# lidar_robot.net
KiCad netlist of a schematic drawn in EAGLE
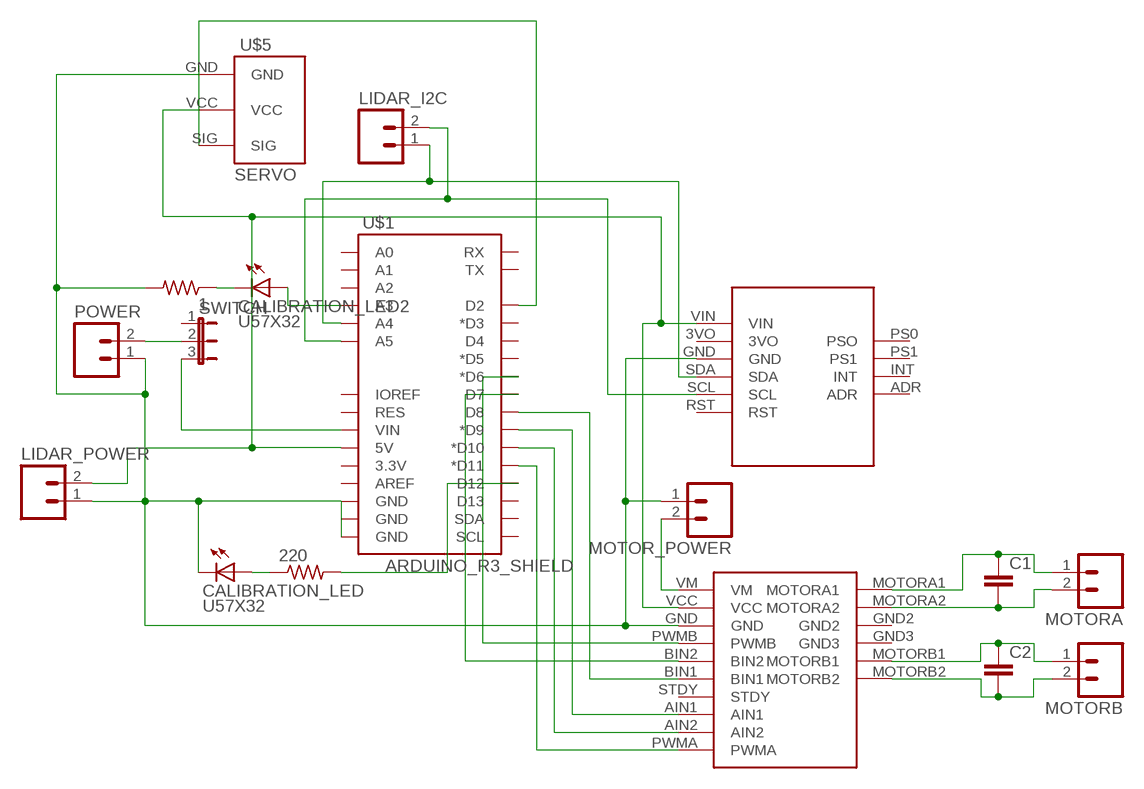
[diagram p0: schematic, sheet 1]

(export (version "E")
  (design (tool "Eeschema 10.0.6"))
  (components
    (comp (ref "1")
      (value "R-US_0207/10")
      (footprint "eagle-import:0207_10")
      (libsource (lib "eagle-import") (part "R-US_0207/10"))
    )
    (comp (ref "220")
      (value "R-US_0207/10")
      (footprint "eagle-import:0207_10")
      (libsource (lib "eagle-import") (part "R-US_0207/10"))
    )
    (comp (ref "C1")
      (value "C2.5/4")
      (footprint "eagle-import:C2.5-4")
      (libsource (lib "eagle-import") (part "C2.5/4"))
    )
    (comp (ref "C2")
      (value "C2.5/4")
      (footprint "eagle-import:C2.5-4")
      (libsource (lib "eagle-import") (part "C2.5/4"))
    )
    (comp (ref "CALIBRATION_LED")
      (value "U57X32")
      (footprint "eagle-import:U57X32")
      (libsource (lib "eagle-import") (part "U57X32"))
    )
    (comp (ref "CALIBRATION_LED2")
      (value "U57X32")
      (footprint "eagle-import:U57X32")
      (libsource (lib "eagle-import") (part "U57X32"))
    )
    (comp (ref "LIDAR_I2C")
      (value "M02LOCK")
      (footprint "eagle-import:1X02_LOCK")
      (libsource (lib "eagle-import") (part "M02LOCK"))
    )
    (comp (ref "LIDAR_POWER")
      (value "M02LOCK")
      (footprint "eagle-import:1X02_LOCK")
      (libsource (lib "eagle-import") (part "M02LOCK"))
    )
    (comp (ref "MOTORA")
      (value "M02LOCK")
      (footprint "eagle-import:1X02_LOCK")
      (libsource (lib "eagle-import") (part "M02LOCK"))
    )
    (comp (ref "MOTORB")
      (value "M02LOCK")
      (footprint "eagle-import:1X02_LOCK")
      (libsource (lib "eagle-import") (part "M02LOCK"))
    )
    (comp (ref "MOTOR_POWER")
      (value "M02LOCK")
      (footprint "eagle-import:1X02_LOCK")
      (libsource (lib "eagle-import") (part "M02LOCK"))
    )
    (comp (ref "POWER")
      (value "M02LOCK")
      (footprint "eagle-import:1X02_LOCK")
      (libsource (lib "eagle-import") (part "M02LOCK"))
    )
    (comp (ref "SWITCH")
      (value "JP2E")
      (footprint "eagle-import:JP2")
      (libsource (lib "eagle-import") (part "JP2E"))
    )
    (comp (ref "U$1")
      (value "ARDUINO_R3_SHIELD")
      (footprint "eagle-import:UNO_R3_SHIELD")
      (libsource (lib "eagle-import") (part "ARDUINO_R3_SHIELD"))
    )
    (comp (ref "U$2")
      (value "BN0055")
      (footprint "eagle-import:BN0055")
      (libsource (lib "eagle-import") (part "BN0055"))
    )
    (comp (ref "U$3")
      (value "TB6612")
      (footprint "eagle-import:TB6612")
      (libsource (lib "eagle-import") (part "TB6612"))
    )
    (comp (ref "U$5")
      (value "SERVO")
      (footprint "eagle-import:SERVO")
      (libsource (lib "eagle-import") (part "SERVO"))
    )
  )
  (nets
    (net (code "1") (name "Net-(220-Pad1)") (class "Default")
      (node (ref "220") (pin "1") (pinfunction "1_1") (pintype "passive"))
      (node (ref "CALIBRATION_LED") (pin "A") (pinfunction "A_A") (pintype "passive"))
    )
    (net (code "2") (name "Net-(220-Pad2)") (class "Default")
      (node (ref "220") (pin "2") (pinfunction "2_2") (pintype "passive"))
      (node (ref "U$1") (pin "D12") (pinfunction "D12_D12") (pintype "bidirectional"))
    )
    (net (code "3") (name "Net-(C1-Pad1)") (class "Default")
      (node (ref "C1") (pin "1") (pinfunction "1_1") (pintype "passive"))
      (node (ref "MOTORA") (pin "1") (pinfunction "1_1") (pintype "passive"))
      (node (ref "U$3") (pin "MOTORA1") (pinfunction "MOTORA1_MOTORA1") (pintype "bidirectional"))
    )
    (net (code "4") (name "Net-(C1-Pad2)") (class "Default")
      (node (ref "C1") (pin "2") (pinfunction "2_2") (pintype "passive"))
      (node (ref "MOTORA") (pin "2") (pinfunction "2_2") (pintype "passive"))
      (node (ref "U$3") (pin "MOTORA2") (pinfunction "MOTORA2_MOTORA2") (pintype "bidirectional"))
    )
    (net (code "5") (name "Net-(C2-Pad1)") (class "Default")
      (node (ref "C2") (pin "1") (pinfunction "1_1") (pintype "passive"))
      (node (ref "MOTORB") (pin "1") (pinfunction "1_1") (pintype "passive"))
      (node (ref "U$3") (pin "MOTORB1") (pinfunction "MOTORB1_MOTORB1") (pintype "bidirectional"))
    )
    (net (code "6") (name "Net-(C2-Pad2)") (class "Default")
      (node (ref "C2") (pin "2") (pinfunction "2_2") (pintype "passive"))
      (node (ref "MOTORB") (pin "2") (pinfunction "2_2") (pintype "passive"))
      (node (ref "U$3") (pin "MOTORB2") (pinfunction "MOTORB2_MOTORB2") (pintype "bidirectional"))
    )
    (net (code "7") (name "Net-(CALIBRATION_LED-C)") (class "Default")
      (node (ref "1") (pin "2") (pinfunction "2_2") (pintype "passive"))
      (node (ref "CALIBRATION_LED") (pin "K") (pinfunction "C_K") (pintype "passive"))
      (node (ref "LIDAR_POWER") (pin "1") (pinfunction "1_1") (pintype "passive"))
      (node (ref "MOTOR_POWER") (pin "1") (pinfunction "1_1") (pintype "passive"))
      (node (ref "POWER") (pin "1") (pinfunction "1_1") (pintype "passive"))
      (node (ref "U$1") (pin "GND@0") (pinfunction "GND_GND@0") (pintype "bidirectional"))
      (node (ref "U$1") (pin "GND@1") (pinfunction "GND_GND@1") (pintype "bidirectional"))
      (node (ref "U$1") (pin "GND@2") (pinfunction "GND_GND@2") (pintype "bidirectional"))
      (node (ref "U$2") (pin "GND") (pinfunction "GND_GND") (pintype "bidirectional"))
      (node (ref "U$3") (pin "GND") (pinfunction "GND_GND") (pintype "bidirectional"))
      (node (ref "U$5") (pin "GND") (pinfunction "GND_GND") (pintype "bidirectional"))
    )
    (net (code "8") (name "Net-(CALIBRATION_LED2-C)") (class "Default")
      (node (ref "1") (pin "1") (pinfunction "1_1") (pintype "passive"))
      (node (ref "CALIBRATION_LED2") (pin "K") (pinfunction "C_K") (pintype "passive"))
    )
    (net (code "9") (name "Net-(CALIBRATION_LED2-PadA)") (class "Default")
      (node (ref "CALIBRATION_LED2") (pin "A") (pinfunction "A_A") (pintype "passive"))
      (node (ref "U$1") (pin "A3") (pinfunction "A3_A3") (pintype "bidirectional"))
    )
    (net (code "10") (name "Net-(LIDAR_I2C-Pad1)") (class "Default")
      (node (ref "LIDAR_I2C") (pin "1") (pinfunction "1_1") (pintype "passive"))
      (node (ref "U$1") (pin "A4") (pinfunction "A4_A4") (pintype "bidirectional"))
      (node (ref "U$2") (pin "SDA") (pinfunction "SDA_SDA") (pintype "bidirectional"))
    )
    (net (code "11") (name "Net-(LIDAR_I2C-Pad2)") (class "Default")
      (node (ref "LIDAR_I2C") (pin "2") (pinfunction "2_2") (pintype "passive"))
      (node (ref "U$1") (pin "A5") (pinfunction "A5_A5") (pintype "bidirectional"))
      (node (ref "U$2") (pin "SCL") (pinfunction "SCL_SCL") (pintype "bidirectional"))
    )
    (net (code "12") (name "Net-(LIDAR_POWER-Pad2)") (class "Default")
      (node (ref "LIDAR_POWER") (pin "2") (pinfunction "2_2") (pintype "passive"))
      (node (ref "U$1") (pin "5V") (pinfunction "5V_5V") (pintype "bidirectional"))
      (node (ref "U$2") (pin "VIN") (pinfunction "VIN_VIN") (pintype "bidirectional"))
      (node (ref "U$3") (pin "VCC") (pinfunction "VCC_VCC") (pintype "bidirectional"))
      (node (ref "U$5") (pin "VCC") (pinfunction "VCC_VCC") (pintype "bidirectional"))
    )
    (net (code "13") (name "Net-(MOTOR_POWER-Pad2)") (class "Default")
      (node (ref "MOTOR_POWER") (pin "2") (pinfunction "2_2") (pintype "passive"))
      (node (ref "U$3") (pin "VM") (pinfunction "VM_VM") (pintype "bidirectional"))
    )
    (net (code "14") (name "Net-(POWER-Pad2)") (class "Default")
      (node (ref "POWER") (pin "2") (pinfunction "2_2") (pintype "passive"))
      (node (ref "SWITCH") (pin "2") (pinfunction "2_2") (pintype "passive"))
    )
    (net (code "15") (name "Net-(SWITCH-Pad3)") (class "Default")
      (node (ref "SWITCH") (pin "3") (pinfunction "3_3") (pintype "passive"))
      (node (ref "U$1") (pin "VIN") (pinfunction "VIN_VIN") (pintype "bidirectional"))
    )
    (net (code "16") (name "Net-(U$1-*D6)") (class "Default")
      (node (ref "U$1") (pin "D6") (pinfunction "*D6_D6") (pintype "bidirectional"))
      (node (ref "U$3") (pin "PWMB") (pinfunction "PWMB_PWMB") (pintype "bidirectional"))
    )
    (net (code "17") (name "Net-(U$1-*D9)") (class "Default")
      (node (ref "U$1") (pin "D9") (pinfunction "*D9_D9") (pintype "bidirectional"))
      (node (ref "U$3") (pin "AIN1") (pinfunction "AIN1_AIN1") (pintype "bidirectional"))
    )
    (net (code "18") (name "Net-(U$1-*D10)") (class "Default")
      (node (ref "U$1") (pin "D10") (pinfunction "*D10_D10") (pintype "bidirectional"))
      (node (ref "U$3") (pin "AIN2") (pinfunction "AIN2_AIN2") (pintype "bidirectional"))
    )
    (net (code "19") (name "Net-(U$1-*D11)") (class "Default")
      (node (ref "U$1") (pin "D11") (pinfunction "*D11_D11") (pintype "bidirectional"))
      (node (ref "U$3") (pin "PWMA") (pinfunction "PWMA_PWMA") (pintype "bidirectional"))
    )
    (net (code "20") (name "Net-(U$1-PadD2)") (class "Default")
      (node (ref "U$1") (pin "D2") (pinfunction "D2_D2") (pintype "bidirectional"))
      (node (ref "U$5") (pin "SIG") (pinfunction "SIG_SIG") (pintype "bidirectional"))
    )
    (net (code "21") (name "Net-(U$1-PadD7)") (class "Default")
      (node (ref "U$1") (pin "D7") (pinfunction "D7_D7") (pintype "bidirectional"))
      (node (ref "U$3") (pin "BIN2") (pinfunction "BIN2_BIN2") (pintype "bidirectional"))
    )
    (net (code "22") (name "Net-(U$1-PadD8)") (class "Default")
      (node (ref "U$1") (pin "D8") (pinfunction "D8_D8") (pintype "bidirectional"))
      (node (ref "U$3") (pin "BIN1") (pinfunction "BIN1_BIN1") (pintype "bidirectional"))
    )
    (net (code "23") (name "unconnected-(SWITCH-Pad1)") (class "Default")
      (node (ref "SWITCH") (pin "1") (pinfunction "1_1") (pintype "passive"))
    )
    (net (code "24") (name "unconnected-(U$1-*D3-PadD3)") (class "Default")
      (node (ref "U$1") (pin "D3") (pinfunction "*D3_D3") (pintype "bidirectional"))
    )
    (net (code "25") (name "unconnected-(U$1-*D5-PadD5)") (class "Default")
      (node (ref "U$1") (pin "D5") (pinfunction "*D5_D5") (pintype "bidirectional"))
    )
    (net (code "26") (name "unconnected-(U$1-Pad3.3V)") (class "Default")
      (node (ref "U$1") (pin "3.3V") (pinfunction "3.3V_3.3V") (pintype "bidirectional"))
    )
    (net (code "27") (name "unconnected-(U$1-PadA0)") (class "Default")
      (node (ref "U$1") (pin "A0") (pinfunction "A0_A0") (pintype "bidirectional"))
    )
    (net (code "28") (name "unconnected-(U$1-PadA1)") (class "Default")
      (node (ref "U$1") (pin "A1") (pinfunction "A1_A1") (pintype "bidirectional"))
    )
    (net (code "29") (name "unconnected-(U$1-PadA2)") (class "Default")
      (node (ref "U$1") (pin "A2") (pinfunction "A2_A2") (pintype "bidirectional"))
    )
    (net (code "30") (name "unconnected-(U$1-PadAREF)") (class "Default")
      (node (ref "U$1") (pin "AREF") (pinfunction "AREF_AREF") (pintype "bidirectional"))
    )
    (net (code "31") (name "unconnected-(U$1-PadD4)") (class "Default")
      (node (ref "U$1") (pin "D4") (pinfunction "D4_D4") (pintype "bidirectional"))
    )
    (net (code "32") (name "unconnected-(U$1-PadD13)") (class "Default")
      (node (ref "U$1") (pin "D13") (pinfunction "D13_D13") (pintype "bidirectional"))
    )
    (net (code "33") (name "unconnected-(U$1-PadIOREF)") (class "Default")
      (node (ref "U$1") (pin "IOREF") (pinfunction "IOREF_IOREF") (pintype "bidirectional"))
    )
    (net (code "34") (name "unconnected-(U$1-PadRES)") (class "Default")
      (node (ref "U$1") (pin "RES") (pinfunction "RES_RES") (pintype "bidirectional"))
    )
    (net (code "35") (name "unconnected-(U$1-PadRX)") (class "Default")
      (node (ref "U$1") (pin "RX") (pinfunction "RX_RX") (pintype "bidirectional"))
    )
    (net (code "36") (name "unconnected-(U$1-PadSCL)") (class "Default")
      (node (ref "U$1") (pin "SCL") (pinfunction "SCL_SCL") (pintype "bidirectional"))
    )
    (net (code "37") (name "unconnected-(U$1-PadSDA)") (class "Default")
      (node (ref "U$1") (pin "SDA") (pinfunction "SDA_SDA") (pintype "bidirectional"))
    )
    (net (code "38") (name "unconnected-(U$1-PadTX)") (class "Default")
      (node (ref "U$1") (pin "TX") (pinfunction "TX_TX") (pintype "bidirectional"))
    )
    (net (code "39") (name "unconnected-(U$2-PSO-PadPS0)") (class "Default")
      (node (ref "U$2") (pin "PS0") (pinfunction "PSO_PS0") (pintype "bidirectional"))
    )
    (net (code "40") (name "unconnected-(U$2-Pad3VO)") (class "Default")
      (node (ref "U$2") (pin "3VO") (pinfunction "3VO_3VO") (pintype "bidirectional"))
    )
    (net (code "41") (name "unconnected-(U$2-PadADR)") (class "Default")
      (node (ref "U$2") (pin "ADR") (pinfunction "ADR_ADR") (pintype "bidirectional"))
    )
    (net (code "42") (name "unconnected-(U$2-PadINT)") (class "Default")
      (node (ref "U$2") (pin "INT") (pinfunction "INT_INT") (pintype "bidirectional"))
    )
    (net (code "43") (name "unconnected-(U$2-PadPS1)") (class "Default")
      (node (ref "U$2") (pin "PS1") (pinfunction "PS1_PS1") (pintype "bidirectional"))
    )
    (net (code "44") (name "unconnected-(U$2-PadRST)") (class "Default")
      (node (ref "U$2") (pin "RST") (pinfunction "RST_RST") (pintype "bidirectional"))
    )
    (net (code "45") (name "unconnected-(U$3-PadGND2)") (class "Default")
      (node (ref "U$3") (pin "GND2") (pinfunction "GND2_GND2") (pintype "bidirectional"))
    )
    (net (code "46") (name "unconnected-(U$3-PadGND3)") (class "Default")
      (node (ref "U$3") (pin "GND3") (pinfunction "GND3_GND3") (pintype "bidirectional"))
    )
    (net (code "47") (name "unconnected-(U$3-PadSTDY)") (class "Default")
      (node (ref "U$3") (pin "STDY") (pinfunction "STDY_STDY") (pintype "bidirectional"))
    )
  )
)
